# Sheet9.net
KiCad netlist of a schematic drawn in Altium Designer
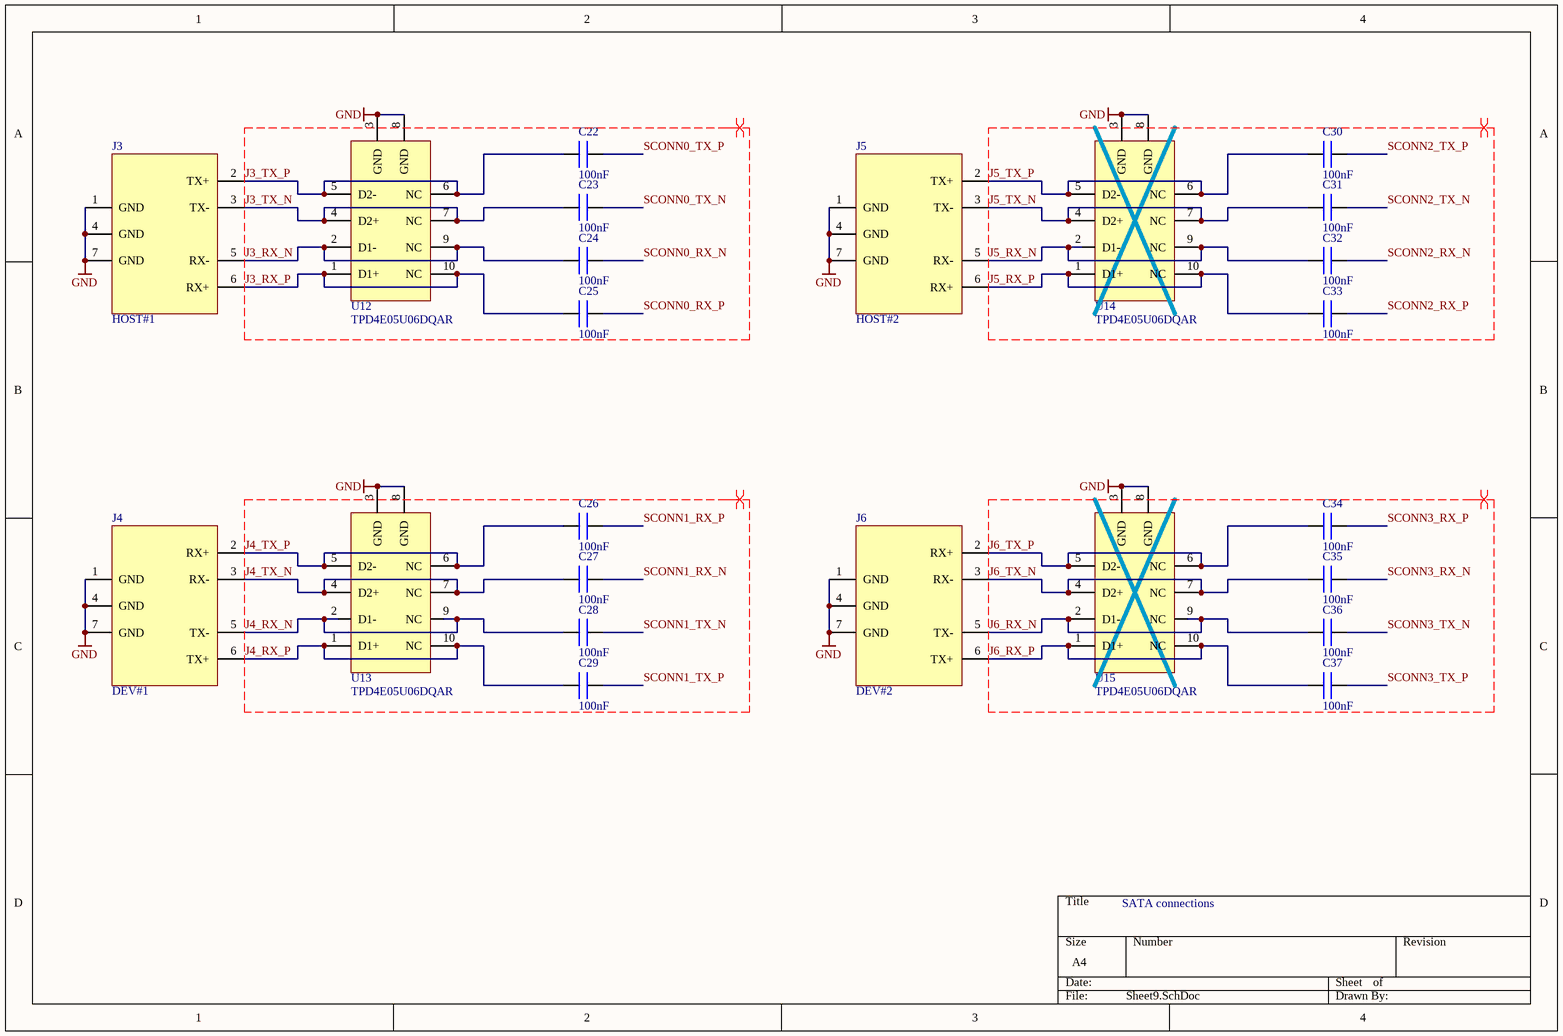
[diagram p0: Sheet9.SchDoc]

(export (version "E")
  (design (tool "Eeschema 10.0.6"))
  (components
    (comp (ref "C22")
      (value "100nF")
      (footprint "CAPC1005X05N")
      (description "Ceramic Chip Capacitor")
      (libsource (lib "Integrated_Library") (part "C0402"))
    )
    (comp (ref "C23")
      (value "100nF")
      (footprint "CAPC1005X05N")
      (description "Ceramic Chip Capacitor")
      (libsource (lib "Integrated_Library") (part "C0402"))
    )
    (comp (ref "C24")
      (value "100nF")
      (footprint "CAPC1005X05N")
      (description "Ceramic Chip Capacitor")
      (libsource (lib "Integrated_Library") (part "C0402"))
    )
    (comp (ref "C25")
      (value "100nF")
      (footprint "CAPC1005X05N")
      (description "Ceramic Chip Capacitor")
      (libsource (lib "Integrated_Library") (part "C0402"))
    )
    (comp (ref "C26")
      (value "100nF")
      (footprint "CAPC1005X05N")
      (description "Ceramic Chip Capacitor")
      (libsource (lib "Integrated_Library") (part "C0402"))
    )
    (comp (ref "C27")
      (value "100nF")
      (footprint "CAPC1005X05N")
      (description "Ceramic Chip Capacitor")
      (libsource (lib "Integrated_Library") (part "C0402"))
    )
    (comp (ref "C28")
      (value "100nF")
      (footprint "CAPC1005X05N")
      (description "Ceramic Chip Capacitor")
      (libsource (lib "Integrated_Library") (part "C0402"))
    )
    (comp (ref "C29")
      (value "100nF")
      (footprint "CAPC1005X05N")
      (description "Ceramic Chip Capacitor")
      (libsource (lib "Integrated_Library") (part "C0402"))
    )
    (comp (ref "C30")
      (value "100nF")
      (footprint "CAPC1005X05N")
      (description "Ceramic Chip Capacitor")
      (libsource (lib "Integrated_Library") (part "C0402"))
    )
    (comp (ref "C31")
      (value "100nF")
      (footprint "CAPC1005X05N")
      (description "Ceramic Chip Capacitor")
      (libsource (lib "Integrated_Library") (part "C0402"))
    )
    (comp (ref "C32")
      (value "100nF")
      (footprint "CAPC1005X05N")
      (description "Ceramic Chip Capacitor")
      (libsource (lib "Integrated_Library") (part "C0402"))
    )
    (comp (ref "C33")
      (value "100nF")
      (footprint "CAPC1005X05N")
      (description "Ceramic Chip Capacitor")
      (libsource (lib "Integrated_Library") (part "C0402"))
    )
    (comp (ref "C34")
      (value "100nF")
      (footprint "CAPC1005X05N")
      (description "Ceramic Chip Capacitor")
      (libsource (lib "Integrated_Library") (part "C0402"))
    )
    (comp (ref "C35")
      (value "100nF")
      (footprint "CAPC1005X05N")
      (description "Ceramic Chip Capacitor")
      (libsource (lib "Integrated_Library") (part "C0402"))
    )
    (comp (ref "C36")
      (value "100nF")
      (footprint "CAPC1005X05N")
      (description "Ceramic Chip Capacitor")
      (libsource (lib "Integrated_Library") (part "C0402"))
    )
    (comp (ref "C37")
      (value "100nF")
      (footprint "CAPC1005X05N")
      (description "Ceramic Chip Capacitor")
      (libsource (lib "Integrated_Library") (part "C0402"))
    )
    (comp (ref "J3")
      (value "HOST#1")
      (footprint "5607-4200-SH")
      (description "3M SATA Series Connector (Host)")
      (libsource (lib "Integrated_Library") (part "5607-4200-SH-HOST"))
    )
    (comp (ref "J4")
      (value "DEV#1")
      (footprint "5607-4200-SH")
      (description "3M SATA Series Connector (Device)")
      (libsource (lib "Integrated_Library") (part "5607-4200-SH-DEVICE"))
    )
    (comp (ref "J5")
      (value "HOST#2")
      (footprint "5607-4200-SH")
      (description "3M SATA Series Connector (Host)")
      (libsource (lib "Integrated_Library") (part "5607-4200-SH-HOST"))
    )
    (comp (ref "J6")
      (value "DEV#2")
      (footprint "5607-4200-SH")
      (description "3M SATA Series Connector (Device)")
      (libsource (lib "Integrated_Library") (part "5607-4200-SH-DEVICE"))
    )
    (comp (ref "U12")
      (value "TPD4E05U06DQAR")
      (footprint "TPD4E05U06DQAR")
      (description "4-Channel ESD Protection Device for Super-Speed (Up to 6 Gbps)  Interface")
      (libsource (lib "Integrated_Library") (part "TPD4E05U06DQAR"))
    )
    (comp (ref "U13")
      (value "TPD4E05U06DQAR")
      (footprint "TPD4E05U06DQAR")
      (description "4-Channel ESD Protection Device for Super-Speed (Up to 6 Gbps)  Interface")
      (libsource (lib "Integrated_Library") (part "TPD4E05U06DQAR"))
    )
    (comp (ref "U14")
      (value "TPD4E05U06DQAR")
      (footprint "TPD4E05U06DQAR")
      (description "4-Channel ESD Protection Device for Super-Speed (Up to 6 Gbps)  Interface")
      (libsource (lib "Integrated_Library") (part "TPD4E05U06DQAR"))
    )
    (comp (ref "U15")
      (value "TPD4E05U06DQAR")
      (footprint "TPD4E05U06DQAR")
      (description "4-Channel ESD Protection Device for Super-Speed (Up to 6 Gbps)  Interface")
      (libsource (lib "Integrated_Library") (part "TPD4E05U06DQAR"))
    )
  )
  (nets
    (net (code "1") (name "/J3_RX_N") (class "Default")
      (node (ref "C24") (pin "2") (pinfunction "2_2") (pintype "passive"))
      (node (ref "J3") (pin "5") (pinfunction "RX-_5") (pintype "passive"))
      (node (ref "U12") (pin "2") (pinfunction "D1-_2") (pintype "passive"))
      (node (ref "U12") (pin "9") (pinfunction "NC_9") (pintype "passive"))
    )
    (net (code "2") (name "/J3_RX_P") (class "Default")
      (node (ref "C25") (pin "2") (pinfunction "2_2") (pintype "passive"))
      (node (ref "J3") (pin "6") (pinfunction "RX+_6") (pintype "passive"))
      (node (ref "U12") (pin "1") (pinfunction "D1+_1") (pintype "passive"))
      (node (ref "U12") (pin "10") (pinfunction "NC_10") (pintype "passive"))
    )
    (net (code "3") (name "/J3_TX_N") (class "Default")
      (node (ref "C23") (pin "2") (pinfunction "2_2") (pintype "passive"))
      (node (ref "J3") (pin "3") (pinfunction "TX-_3") (pintype "passive"))
      (node (ref "U12") (pin "4") (pinfunction "D2+_4") (pintype "passive"))
      (node (ref "U12") (pin "7") (pinfunction "NC_7") (pintype "passive"))
    )
    (net (code "4") (name "/J3_TX_P") (class "Default")
      (node (ref "C22") (pin "2") (pinfunction "2_2") (pintype "passive"))
      (node (ref "J3") (pin "2") (pinfunction "TX+_2") (pintype "passive"))
      (node (ref "U12") (pin "5") (pinfunction "D2-_5") (pintype "passive"))
      (node (ref "U12") (pin "6") (pinfunction "NC_6") (pintype "passive"))
    )
    (net (code "5") (name "/J4_RX_N") (class "Default")
      (node (ref "C28") (pin "2") (pinfunction "2_2") (pintype "passive"))
      (node (ref "J4") (pin "5") (pinfunction "TX-_5") (pintype "passive"))
      (node (ref "U13") (pin "2") (pinfunction "D1-_2") (pintype "passive"))
      (node (ref "U13") (pin "9") (pinfunction "NC_9") (pintype "passive"))
    )
    (net (code "6") (name "/J4_RX_P") (class "Default")
      (node (ref "C29") (pin "2") (pinfunction "2_2") (pintype "passive"))
      (node (ref "J4") (pin "6") (pinfunction "TX+_6") (pintype "passive"))
      (node (ref "U13") (pin "1") (pinfunction "D1+_1") (pintype "passive"))
      (node (ref "U13") (pin "10") (pinfunction "NC_10") (pintype "passive"))
    )
    (net (code "7") (name "/J4_TX_N") (class "Default")
      (node (ref "C27") (pin "2") (pinfunction "2_2") (pintype "passive"))
      (node (ref "J4") (pin "3") (pinfunction "RX-_3") (pintype "passive"))
      (node (ref "U13") (pin "4") (pinfunction "D2+_4") (pintype "passive"))
      (node (ref "U13") (pin "7") (pinfunction "NC_7") (pintype "passive"))
    )
    (net (code "8") (name "/J4_TX_P") (class "Default")
      (node (ref "C26") (pin "2") (pinfunction "2_2") (pintype "passive"))
      (node (ref "J4") (pin "2") (pinfunction "RX+_2") (pintype "passive"))
      (node (ref "U13") (pin "5") (pinfunction "D2-_5") (pintype "passive"))
      (node (ref "U13") (pin "6") (pinfunction "NC_6") (pintype "passive"))
    )
    (net (code "9") (name "/J5_RX_N") (class "Default")
      (node (ref "C32") (pin "2") (pinfunction "2_2") (pintype "passive"))
      (node (ref "J5") (pin "5") (pinfunction "RX-_5") (pintype "passive"))
      (node (ref "U14") (pin "2") (pinfunction "D1-_2") (pintype "passive"))
      (node (ref "U14") (pin "9") (pinfunction "NC_9") (pintype "passive"))
    )
    (net (code "10") (name "/J5_RX_P") (class "Default")
      (node (ref "C33") (pin "2") (pinfunction "2_2") (pintype "passive"))
      (node (ref "J5") (pin "6") (pinfunction "RX+_6") (pintype "passive"))
      (node (ref "U14") (pin "1") (pinfunction "D1+_1") (pintype "passive"))
      (node (ref "U14") (pin "10") (pinfunction "NC_10") (pintype "passive"))
    )
    (net (code "11") (name "/J5_TX_N") (class "Default")
      (node (ref "C31") (pin "2") (pinfunction "2_2") (pintype "passive"))
      (node (ref "J5") (pin "3") (pinfunction "TX-_3") (pintype "passive"))
      (node (ref "U14") (pin "4") (pinfunction "D2+_4") (pintype "passive"))
      (node (ref "U14") (pin "7") (pinfunction "NC_7") (pintype "passive"))
    )
    (net (code "12") (name "/J5_TX_P") (class "Default")
      (node (ref "C30") (pin "2") (pinfunction "2_2") (pintype "passive"))
      (node (ref "J5") (pin "2") (pinfunction "TX+_2") (pintype "passive"))
      (node (ref "U14") (pin "5") (pinfunction "D2-_5") (pintype "passive"))
      (node (ref "U14") (pin "6") (pinfunction "NC_6") (pintype "passive"))
    )
    (net (code "13") (name "/J6_RX_N") (class "Default")
      (node (ref "C36") (pin "2") (pinfunction "2_2") (pintype "passive"))
      (node (ref "J6") (pin "5") (pinfunction "TX-_5") (pintype "passive"))
      (node (ref "U15") (pin "2") (pinfunction "D1-_2") (pintype "passive"))
      (node (ref "U15") (pin "9") (pinfunction "NC_9") (pintype "passive"))
    )
    (net (code "14") (name "/J6_RX_P") (class "Default")
      (node (ref "C37") (pin "2") (pinfunction "2_2") (pintype "passive"))
      (node (ref "J6") (pin "6") (pinfunction "TX+_6") (pintype "passive"))
      (node (ref "U15") (pin "1") (pinfunction "D1+_1") (pintype "passive"))
      (node (ref "U15") (pin "10") (pinfunction "NC_10") (pintype "passive"))
    )
    (net (code "15") (name "/J6_TX_N") (class "Default")
      (node (ref "C35") (pin "2") (pinfunction "2_2") (pintype "passive"))
      (node (ref "J6") (pin "3") (pinfunction "RX-_3") (pintype "passive"))
      (node (ref "U15") (pin "4") (pinfunction "D2+_4") (pintype "passive"))
      (node (ref "U15") (pin "7") (pinfunction "NC_7") (pintype "passive"))
    )
    (net (code "16") (name "/J6_TX_P") (class "Default")
      (node (ref "C34") (pin "2") (pinfunction "2_2") (pintype "passive"))
      (node (ref "J6") (pin "2") (pinfunction "RX+_2") (pintype "passive"))
      (node (ref "U15") (pin "5") (pinfunction "D2-_5") (pintype "passive"))
      (node (ref "U15") (pin "6") (pinfunction "NC_6") (pintype "passive"))
    )
    (net (code "17") (name "/SCONN0_RX_N") (class "Default")
      (node (ref "C24") (pin "1") (pinfunction "1_1") (pintype "passive"))
    )
    (net (code "18") (name "/SCONN0_RX_P") (class "Default")
      (node (ref "C25") (pin "1") (pinfunction "1_1") (pintype "passive"))
    )
    (net (code "19") (name "/SCONN0_TX_N") (class "Default")
      (node (ref "C23") (pin "1") (pinfunction "1_1") (pintype "passive"))
    )
    (net (code "20") (name "/SCONN0_TX_P") (class "Default")
      (node (ref "C22") (pin "1") (pinfunction "1_1") (pintype "passive"))
    )
    (net (code "21") (name "/SCONN1_RX_N") (class "Default")
      (node (ref "C27") (pin "1") (pinfunction "1_1") (pintype "passive"))
    )
    (net (code "22") (name "/SCONN1_RX_P") (class "Default")
      (node (ref "C26") (pin "1") (pinfunction "1_1") (pintype "passive"))
    )
    (net (code "23") (name "/SCONN1_TX_N") (class "Default")
      (node (ref "C28") (pin "1") (pinfunction "1_1") (pintype "passive"))
    )
    (net (code "24") (name "/SCONN1_TX_P") (class "Default")
      (node (ref "C29") (pin "1") (pinfunction "1_1") (pintype "passive"))
    )
    (net (code "25") (name "/SCONN2_RX_N") (class "Default")
      (node (ref "C32") (pin "1") (pinfunction "1_1") (pintype "passive"))
    )
    (net (code "26") (name "/SCONN2_RX_P") (class "Default")
      (node (ref "C33") (pin "1") (pinfunction "1_1") (pintype "passive"))
    )
    (net (code "27") (name "/SCONN2_TX_N") (class "Default")
      (node (ref "C31") (pin "1") (pinfunction "1_1") (pintype "passive"))
    )
    (net (code "28") (name "/SCONN2_TX_P") (class "Default")
      (node (ref "C30") (pin "1") (pinfunction "1_1") (pintype "passive"))
    )
    (net (code "29") (name "/SCONN3_RX_N") (class "Default")
      (node (ref "C35") (pin "1") (pinfunction "1_1") (pintype "passive"))
    )
    (net (code "30") (name "/SCONN3_RX_P") (class "Default")
      (node (ref "C34") (pin "1") (pinfunction "1_1") (pintype "passive"))
    )
    (net (code "31") (name "/SCONN3_TX_N") (class "Default")
      (node (ref "C36") (pin "1") (pinfunction "1_1") (pintype "passive"))
    )
    (net (code "32") (name "/SCONN3_TX_P") (class "Default")
      (node (ref "C37") (pin "1") (pinfunction "1_1") (pintype "passive"))
    )
    (net (code "33") (name "GND") (class "Default")
      (node (ref "J3") (pin "1") (pinfunction "GND_1") (pintype "power_in"))
      (node (ref "J3") (pin "4") (pinfunction "GND_4") (pintype "power_in"))
      (node (ref "J3") (pin "7") (pinfunction "GND_7") (pintype "power_in"))
      (node (ref "J4") (pin "1") (pinfunction "GND_1") (pintype "power_in"))
      (node (ref "J4") (pin "4") (pinfunction "GND_4") (pintype "power_in"))
      (node (ref "J4") (pin "7") (pinfunction "GND_7") (pintype "power_in"))
      (node (ref "J5") (pin "1") (pinfunction "GND_1") (pintype "power_in"))
      (node (ref "J5") (pin "4") (pinfunction "GND_4") (pintype "power_in"))
      (node (ref "J5") (pin "7") (pinfunction "GND_7") (pintype "power_in"))
      (node (ref "J6") (pin "1") (pinfunction "GND_1") (pintype "power_in"))
      (node (ref "J6") (pin "4") (pinfunction "GND_4") (pintype "power_in"))
      (node (ref "J6") (pin "7") (pinfunction "GND_7") (pintype "power_in"))
      (node (ref "U12") (pin "3") (pinfunction "GND_3") (pintype "power_in"))
      (node (ref "U12") (pin "8") (pinfunction "GND_8") (pintype "power_in"))
      (node (ref "U13") (pin "3") (pinfunction "GND_3") (pintype "power_in"))
      (node (ref "U13") (pin "8") (pinfunction "GND_8") (pintype "power_in"))
      (node (ref "U14") (pin "3") (pinfunction "GND_3") (pintype "power_in"))
      (node (ref "U14") (pin "8") (pinfunction "GND_8") (pintype "power_in"))
      (node (ref "U15") (pin "3") (pinfunction "GND_3") (pintype "power_in"))
      (node (ref "U15") (pin "8") (pinfunction "GND_8") (pintype "power_in"))
    )
  )
)
